# LB_BIT_1IN_3OUT-SMALL-v03_1_1x.net
KiCad netlist of a schematic drawn in EAGLE
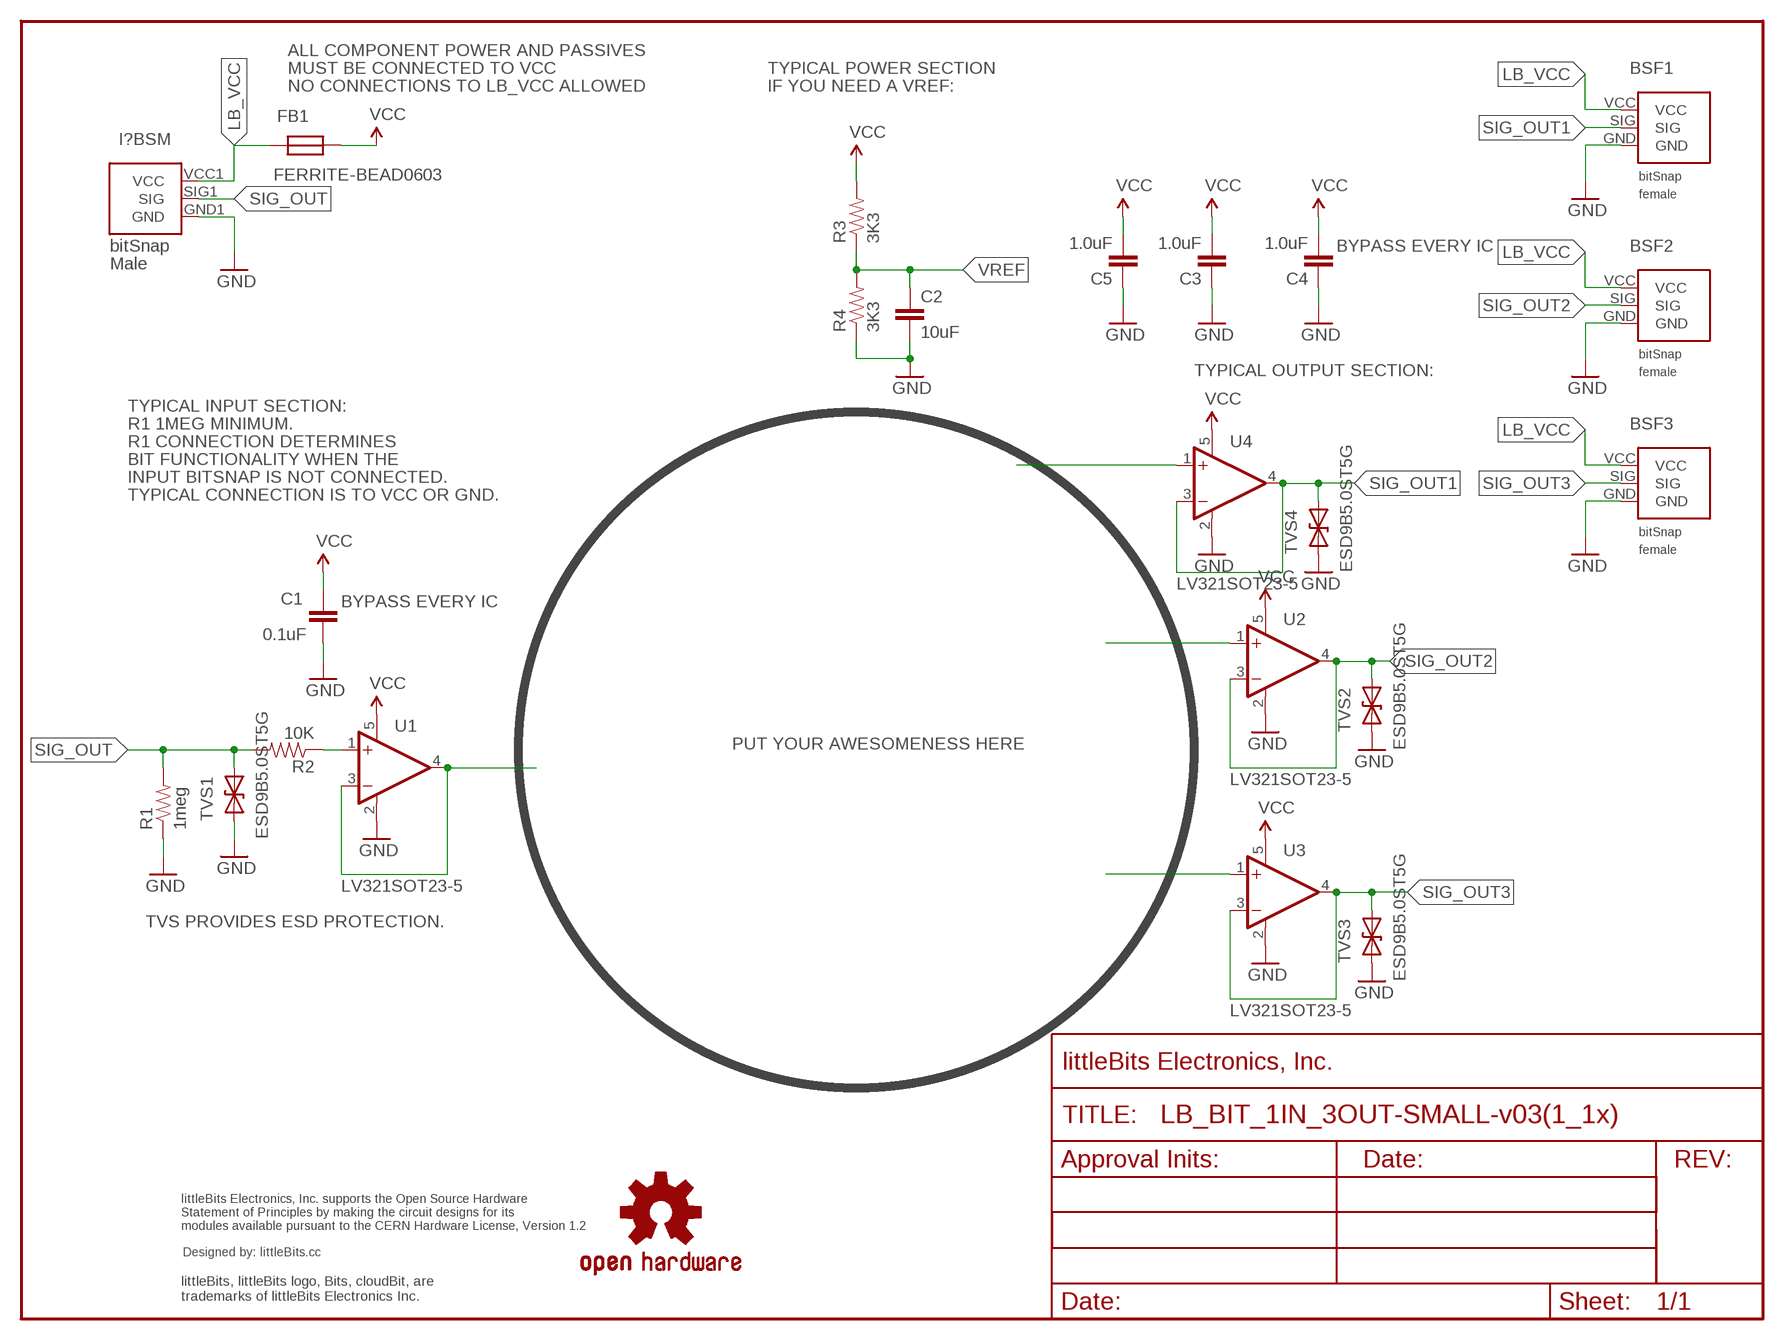
[diagram p0: schematic, sheet 1]

(export (version "E")
  (design (tool "Eeschema 10.0.6"))
  (components
    (comp (ref "BSF1")
      (value "BITSNAP_V03_FEMALE")
      (footprint "eagle-import:BITSNAP_V03_FEMALE")
      (libsource (lib "eagle-import") (part "BITSNAP_V03_FEMALE"))
    )
    (comp (ref "BSF2")
      (value "BITSNAP_V03_FEMALE")
      (footprint "eagle-import:BITSNAP_V03_FEMALE")
      (libsource (lib "eagle-import") (part "BITSNAP_V03_FEMALE"))
    )
    (comp (ref "BSF3")
      (value "BITSNAP_V03_FEMALE")
      (footprint "eagle-import:BITSNAP_V03_FEMALE")
      (libsource (lib "eagle-import") (part "BITSNAP_V03_FEMALE"))
    )
    (comp (ref "C1")
      (value "0.1uF")
      (footprint "eagle-import:CAP-0603")
      (libsource (lib "eagle-import") (part "CAPCAP-0603"))
    )
    (comp (ref "C2")
      (value "10uF")
      (footprint "eagle-import:CAP-0603")
      (libsource (lib "eagle-import") (part "CAPCAP-0603"))
    )
    (comp (ref "C3")
      (value "1.0uF")
      (footprint "eagle-import:CAP-0603")
      (libsource (lib "eagle-import") (part "CAPCAP-0603"))
    )
    (comp (ref "C4")
      (value "1.0uF")
      (footprint "eagle-import:CAP-0603")
      (libsource (lib "eagle-import") (part "CAPCAP-0603"))
    )
    (comp (ref "C5")
      (value "1.0uF")
      (footprint "eagle-import:CAP-0603")
      (libsource (lib "eagle-import") (part "CAPCAP-0603"))
    )
    (comp (ref "FB1")
      (value "FERRITE-BEAD0603")
      (footprint "eagle-import:R0603")
      (libsource (lib "eagle-import") (part "FERRITE-BEAD0603"))
    )
    (comp (ref "FRAME1")
      (value "FRAME-LETTER")
      (footprint "eagle-import:FABDWG01-OHW")
      (libsource (lib "eagle-import") (part "FRAME-LETTER"))
    )
    (comp (ref "I?BSM")
      (value "BITSNAP_V03_MALE")
      (footprint "eagle-import:BITSNAP_V03_MALE")
      (libsource (lib "eagle-import") (part "BITSNAP_V03_MALE"))
    )
    (comp (ref "R1")
      (value "1meg")
      (footprint "eagle-import:RES-0603")
      (libsource (lib "eagle-import") (part "RESISTOR0603"))
    )
    (comp (ref "R2")
      (value "10K")
      (footprint "eagle-import:RES-0603")
      (libsource (lib "eagle-import") (part "RESISTOR0603"))
    )
    (comp (ref "R3")
      (value "3K3")
      (footprint "eagle-import:RES-0603")
      (libsource (lib "eagle-import") (part "RESISTOR0603"))
    )
    (comp (ref "R4")
      (value "3K3")
      (footprint "eagle-import:RES-0603")
      (libsource (lib "eagle-import") (part "RESISTOR0603"))
    )
    (comp (ref "TVS1")
      (value "ESD9B5.0ST5G")
      (footprint "eagle-import:SOD-923")
      (libsource (lib "eagle-import") (part "DIODE-TVSSOD-923"))
    )
    (comp (ref "TVS2")
      (value "ESD9B5.0ST5G")
      (footprint "eagle-import:SOD-923")
      (libsource (lib "eagle-import") (part "DIODE-TVSSOD-923"))
    )
    (comp (ref "TVS3")
      (value "ESD9B5.0ST5G")
      (footprint "eagle-import:SOD-923")
      (libsource (lib "eagle-import") (part "DIODE-TVSSOD-923"))
    )
    (comp (ref "TVS4")
      (value "ESD9B5.0ST5G")
      (footprint "eagle-import:SOD-923")
      (libsource (lib "eagle-import") (part "DIODE-TVSSOD-923"))
    )
    (comp (ref "U$1")
      (value "OSHWCREDIT")
      (footprint "eagle-import:OSHWCREDIT")
      (libsource (lib "eagle-import") (part "OSHWCREDIT"))
    )
    (comp (ref "U$3")
      (value "OSHW-LOGOL")
      (footprint "eagle-import:OSHW-LOGO-L")
      (libsource (lib "eagle-import") (part "OSHW-LOGOL"))
    )
    (comp (ref "U1")
      (value "LV321SOT23-5")
      (footprint "eagle-import:SOT23-5")
      (libsource (lib "eagle-import") (part "LV321SOT23-5"))
    )
    (comp (ref "U2")
      (value "LV321SOT23-5")
      (footprint "eagle-import:SOT23-5")
      (libsource (lib "eagle-import") (part "LV321SOT23-5"))
    )
    (comp (ref "U3")
      (value "LV321SOT23-5")
      (footprint "eagle-import:SOT23-5")
      (libsource (lib "eagle-import") (part "LV321SOT23-5"))
    )
    (comp (ref "U4")
      (value "LV321SOT23-5")
      (footprint "eagle-import:SOT23-5")
      (libsource (lib "eagle-import") (part "LV321SOT23-5"))
    )
  )
  (nets
    (net (code "1") (name "GND") (class "Default")
      (node (ref "BSF1") (pin "GND") (pinfunction "GND_GND") (pintype "bidirectional"))
      (node (ref "BSF2") (pin "GND") (pinfunction "GND_GND") (pintype "bidirectional"))
      (node (ref "BSF3") (pin "GND") (pinfunction "GND_GND") (pintype "bidirectional"))
      (node (ref "C1") (pin "2") (pinfunction "2_2") (pintype "passive"))
      (node (ref "C2") (pin "2") (pinfunction "2_2") (pintype "passive"))
      (node (ref "C3") (pin "1") (pinfunction "1_1") (pintype "passive"))
      (node (ref "C4") (pin "1") (pinfunction "1_1") (pintype "passive"))
      (node (ref "C5") (pin "1") (pinfunction "1_1") (pintype "passive"))
      (node (ref "I?BSM") (pin "GND1") (pinfunction "GND_GND1") (pintype "bidirectional"))
      (node (ref "R1") (pin "1") (pinfunction "1_1") (pintype "passive"))
      (node (ref "R4") (pin "1") (pinfunction "1_1") (pintype "passive"))
      (node (ref "TVS1") (pin "1") (pinfunction "A_1") (pintype "passive"))
      (node (ref "TVS2") (pin "1") (pinfunction "A_1") (pintype "passive"))
      (node (ref "TVS3") (pin "1") (pinfunction "A_1") (pintype "passive"))
      (node (ref "TVS4") (pin "1") (pinfunction "A_1") (pintype "passive"))
      (node (ref "U1") (pin "2") (pinfunction "V-_2") (pintype "power_in"))
      (node (ref "U2") (pin "2") (pinfunction "V-_2") (pintype "power_in"))
      (node (ref "U3") (pin "2") (pinfunction "V-_2") (pintype "power_in"))
      (node (ref "U4") (pin "2") (pinfunction "V-_2") (pintype "power_in"))
    )
    (net (code "2") (name "LB_VCC") (class "Default")
      (node (ref "BSF1") (pin "VCC") (pinfunction "VCC_VCC") (pintype "bidirectional"))
      (node (ref "BSF2") (pin "VCC") (pinfunction "VCC_VCC") (pintype "bidirectional"))
      (node (ref "BSF3") (pin "VCC") (pinfunction "VCC_VCC") (pintype "bidirectional"))
      (node (ref "FB1") (pin "2") (pinfunction "P$2_2") (pintype "bidirectional"))
      (node (ref "I?BSM") (pin "VCC1") (pinfunction "VCC_VCC1") (pintype "bidirectional"))
    )
    (net (code "3") (name "Net-(U1-+IN)") (class "Default")
      (node (ref "R2") (pin "1") (pinfunction "1_1") (pintype "passive"))
      (node (ref "U1") (pin "1") (pinfunction "+IN_1") (pintype "input"))
    )
    (net (code "4") (name "Net-(U1--IN)") (class "Default")
      (node (ref "U1") (pin "3") (pinfunction "-IN_3") (pintype "input"))
      (node (ref "U1") (pin "4") (pinfunction "OUT_4") (pintype "output"))
    )
    (net (code "5") (name "SIG_OUT") (class "Default")
      (node (ref "I?BSM") (pin "SIG1") (pinfunction "SIG_SIG1") (pintype "bidirectional"))
      (node (ref "R1") (pin "2") (pinfunction "2_2") (pintype "passive"))
      (node (ref "R2") (pin "2") (pinfunction "2_2") (pintype "passive"))
      (node (ref "TVS1") (pin "2") (pinfunction "C_2") (pintype "passive"))
    )
    (net (code "6") (name "SIG_OUT1") (class "Default")
      (node (ref "BSF1") (pin "SIG") (pinfunction "SIG_SIG") (pintype "bidirectional"))
      (node (ref "TVS4") (pin "2") (pinfunction "C_2") (pintype "passive"))
      (node (ref "U4") (pin "3") (pinfunction "-IN_3") (pintype "input"))
      (node (ref "U4") (pin "4") (pinfunction "OUT_4") (pintype "output"))
    )
    (net (code "7") (name "SIG_OUT2") (class "Default")
      (node (ref "BSF2") (pin "SIG") (pinfunction "SIG_SIG") (pintype "bidirectional"))
      (node (ref "TVS2") (pin "2") (pinfunction "C_2") (pintype "passive"))
      (node (ref "U2") (pin "3") (pinfunction "-IN_3") (pintype "input"))
      (node (ref "U2") (pin "4") (pinfunction "OUT_4") (pintype "output"))
    )
    (net (code "8") (name "SIG_OUT3") (class "Default")
      (node (ref "BSF3") (pin "SIG") (pinfunction "SIG_SIG") (pintype "bidirectional"))
      (node (ref "TVS3") (pin "2") (pinfunction "C_2") (pintype "passive"))
      (node (ref "U3") (pin "3") (pinfunction "-IN_3") (pintype "input"))
      (node (ref "U3") (pin "4") (pinfunction "OUT_4") (pintype "output"))
    )
    (net (code "9") (name "VCC") (class "Default")
      (node (ref "C1") (pin "1") (pinfunction "1_1") (pintype "passive"))
      (node (ref "C3") (pin "2") (pinfunction "2_2") (pintype "passive"))
      (node (ref "C4") (pin "2") (pinfunction "2_2") (pintype "passive"))
      (node (ref "C5") (pin "2") (pinfunction "2_2") (pintype "passive"))
      (node (ref "FB1") (pin "1") (pinfunction "P$1_1") (pintype "bidirectional"))
      (node (ref "R3") (pin "2") (pinfunction "2_2") (pintype "passive"))
      (node (ref "U1") (pin "5") (pinfunction "V+_5") (pintype "power_in"))
      (node (ref "U2") (pin "5") (pinfunction "V+_5") (pintype "power_in"))
      (node (ref "U3") (pin "5") (pinfunction "V+_5") (pintype "power_in"))
      (node (ref "U4") (pin "5") (pinfunction "V+_5") (pintype "power_in"))
    )
    (net (code "10") (name "VREF") (class "Default")
      (node (ref "C2") (pin "1") (pinfunction "1_1") (pintype "passive"))
      (node (ref "R3") (pin "1") (pinfunction "1_1") (pintype "passive"))
      (node (ref "R4") (pin "2") (pinfunction "2_2") (pintype "passive"))
    )
    (net (code "11") (name "unconnected-(U2-+IN-Pad1)") (class "Default")
      (node (ref "U2") (pin "1") (pinfunction "+IN_1") (pintype "input"))
    )
    (net (code "12") (name "unconnected-(U3-+IN-Pad1)") (class "Default")
      (node (ref "U3") (pin "1") (pinfunction "+IN_1") (pintype "input"))
    )
    (net (code "13") (name "unconnected-(U4-+IN-Pad1)") (class "Default")
      (node (ref "U4") (pin "1") (pinfunction "+IN_1") (pintype "input"))
    )
  )
)
